# programmer.net
KiCad netlist of a schematic drawn in EAGLE
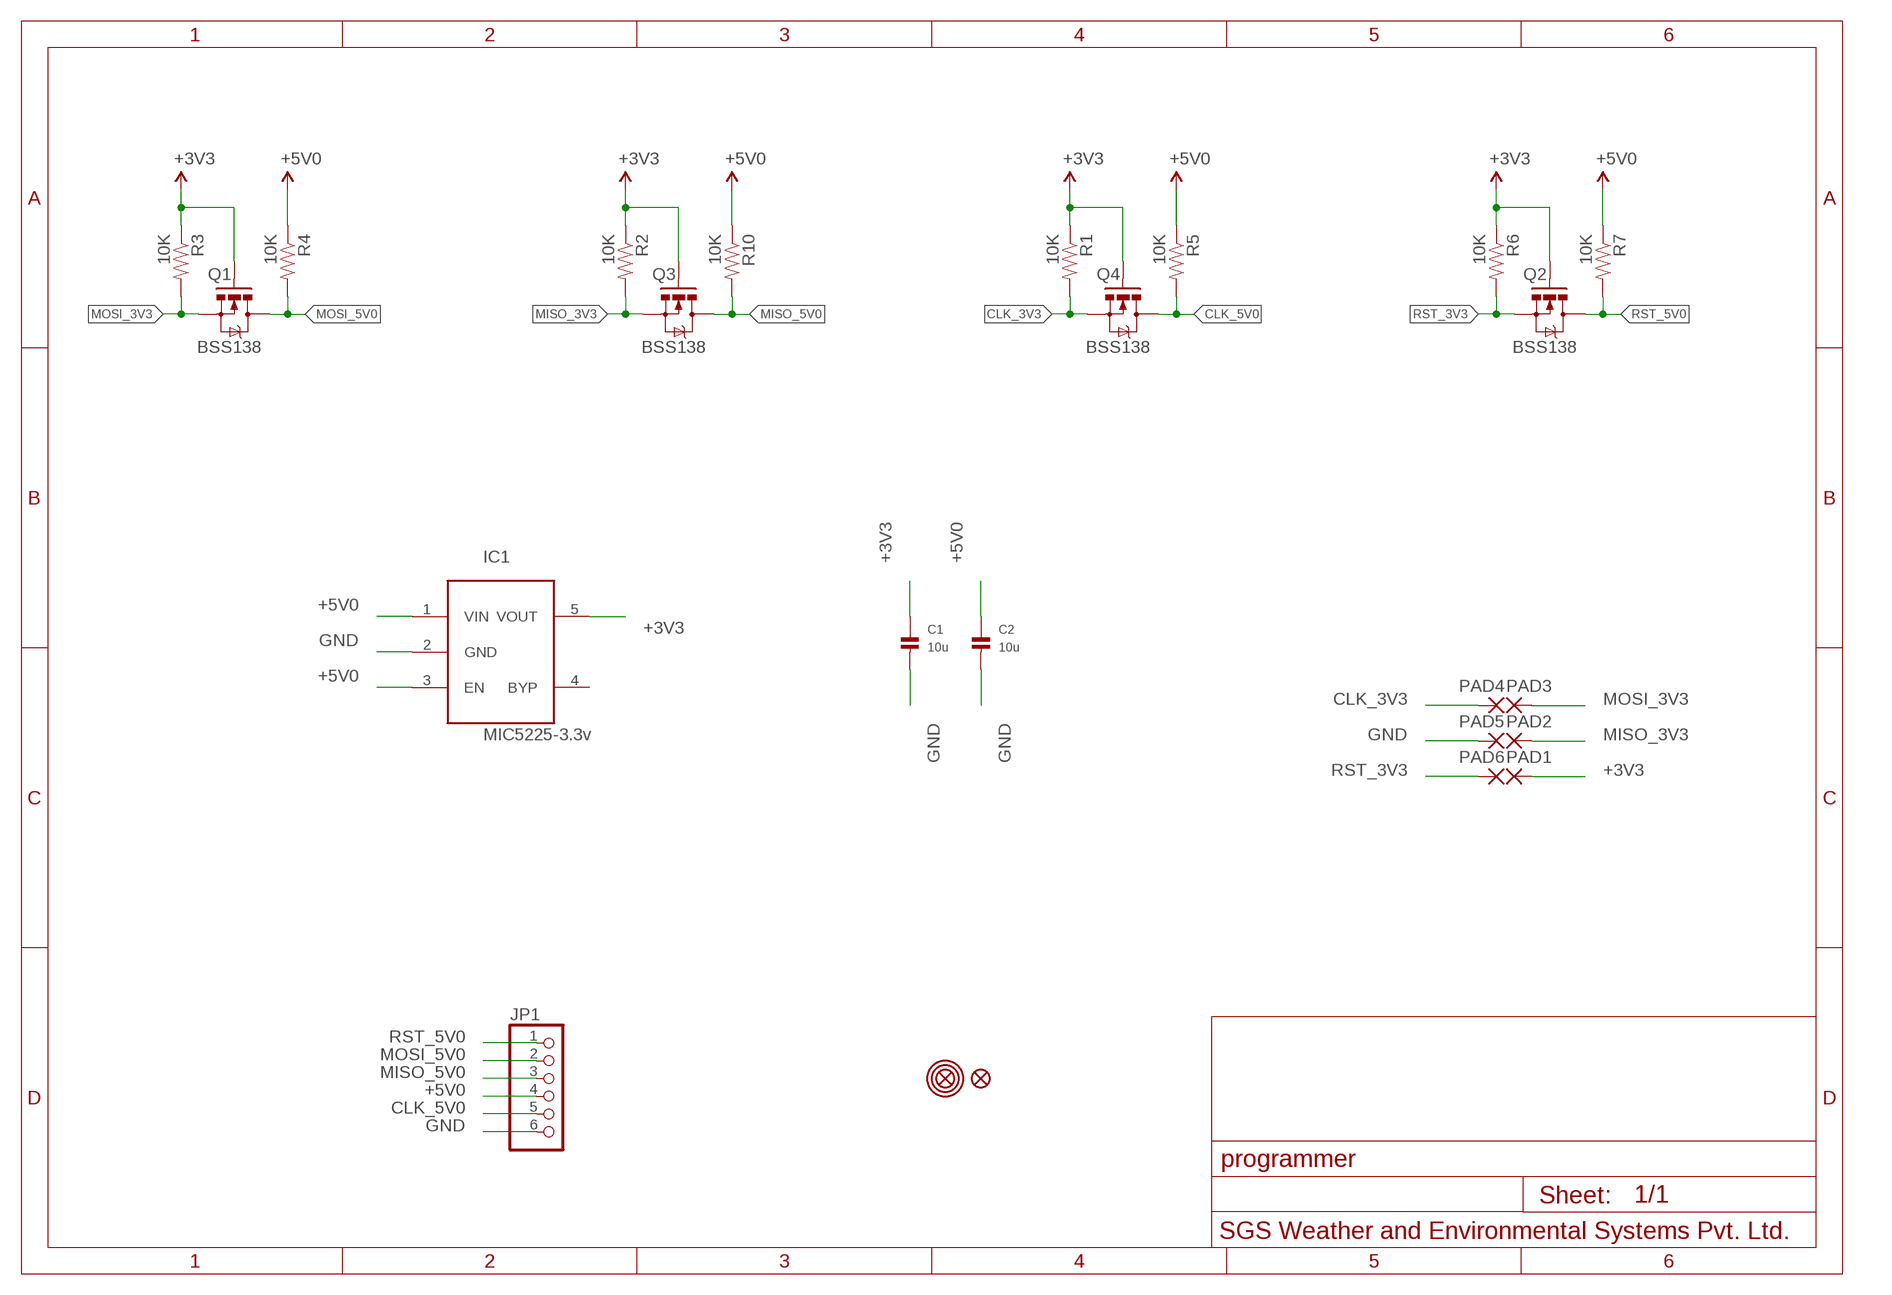
[diagram p0: schematic, sheet 1]

(export (version "E")
  (design (tool "Eeschema 10.0.6"))
  (components
    (comp (ref "C1")
      (value "10u")
      (footprint "eagle-import:0603")
      (libsource (lib "eagle-import") (part "CAP_CERAMIC0603"))
    )
    (comp (ref "C2")
      (value "10u")
      (footprint "eagle-import:0603")
      (libsource (lib "eagle-import") (part "CAP_CERAMIC0603"))
    )
    (comp (ref "FID1")
      (value "FIDUCIAL1X2.5")
      (footprint "eagle-import:FIDUCIAL-1X2.5")
      (libsource (lib "eagle-import") (part "FIDUCIAL1X2.5"))
    )
    (comp (ref "FID2")
      (value "FIDUCIAL1X2.5")
      (footprint "eagle-import:FIDUCIAL-1X2.5")
      (libsource (lib "eagle-import") (part "FIDUCIAL1X2.5"))
    )
    (comp (ref "IC1")
      (value "MIC5225-3.3v")
      (footprint "eagle-import:SOT23-5L")
      (libsource (lib "eagle-import") (part "LP298XS"))
    )
    (comp (ref "JP1")
      (value "HEADER-1X6ROUND")
      (footprint "eagle-import:1X06_ROUND")
      (libsource (lib "eagle-import") (part "HEADER-1X6ROUND"))
    )
    (comp (ref "PAD1")
      (value "WIREPADSMD1,27-254")
      (footprint "eagle-import:SMD1,27-2,54")
      (libsource (lib "eagle-import") (part "WIREPADSMD1,27-254"))
    )
    (comp (ref "PAD2")
      (value "WIREPADSMD1,27-254")
      (footprint "eagle-import:SMD1,27-2,54")
      (libsource (lib "eagle-import") (part "WIREPADSMD1,27-254"))
    )
    (comp (ref "PAD3")
      (value "WIREPADSMD1,27-254")
      (footprint "eagle-import:SMD1,27-2,54")
      (libsource (lib "eagle-import") (part "WIREPADSMD1,27-254"))
    )
    (comp (ref "PAD4")
      (value "WIREPADSMD1,27-254")
      (footprint "eagle-import:SMD1,27-2,54")
      (libsource (lib "eagle-import") (part "WIREPADSMD1,27-254"))
    )
    (comp (ref "PAD5")
      (value "WIREPADSMD1,27-254")
      (footprint "eagle-import:SMD1,27-2,54")
      (libsource (lib "eagle-import") (part "WIREPADSMD1,27-254"))
    )
    (comp (ref "PAD6")
      (value "WIREPADSMD1,27-254")
      (footprint "eagle-import:SMD1,27-2,54")
      (libsource (lib "eagle-import") (part "WIREPADSMD1,27-254"))
    )
    (comp (ref "Q1")
      (value "BSS138")
      (footprint "eagle-import:SOT23-3")
      (libsource (lib "eagle-import") (part "MOSFET-NCHANNELSMD"))
    )
    (comp (ref "Q2")
      (value "BSS138")
      (footprint "eagle-import:SOT23-3")
      (libsource (lib "eagle-import") (part "MOSFET-NCHANNELSMD"))
    )
    (comp (ref "Q3")
      (value "BSS138")
      (footprint "eagle-import:SOT23-3")
      (libsource (lib "eagle-import") (part "MOSFET-NCHANNELSMD"))
    )
    (comp (ref "Q4")
      (value "BSS138")
      (footprint "eagle-import:SOT23-3")
      (libsource (lib "eagle-import") (part "MOSFET-NCHANNELSMD"))
    )
    (comp (ref "R1")
      (value "10K")
      (footprint "eagle-import:0603-RES")
      (libsource (lib "eagle-import") (part "RESISTOR0603-RES"))
    )
    (comp (ref "R2")
      (value "10K")
      (footprint "eagle-import:0603-RES")
      (libsource (lib "eagle-import") (part "RESISTOR0603-RES"))
    )
    (comp (ref "R3")
      (value "10K")
      (footprint "eagle-import:0603-RES")
      (libsource (lib "eagle-import") (part "RESISTOR0603-RES"))
    )
    (comp (ref "R4")
      (value "10K")
      (footprint "eagle-import:0603-RES")
      (libsource (lib "eagle-import") (part "RESISTOR0603-RES"))
    )
    (comp (ref "R5")
      (value "10K")
      (footprint "eagle-import:0603-RES")
      (libsource (lib "eagle-import") (part "RESISTOR0603-RES"))
    )
    (comp (ref "R6")
      (value "10K")
      (footprint "eagle-import:0603-RES")
      (libsource (lib "eagle-import") (part "RESISTOR0603-RES"))
    )
    (comp (ref "R7")
      (value "10K")
      (footprint "eagle-import:0603-RES")
      (libsource (lib "eagle-import") (part "RESISTOR0603-RES"))
    )
    (comp (ref "R10")
      (value "10K")
      (footprint "eagle-import:0603-RES")
      (libsource (lib "eagle-import") (part "RESISTOR0603-RES"))
    )
    (comp (ref "U$1")
      (value "MOUNTINGHOLE2.5")
      (footprint "eagle-import:MOUNTINGHOLE_2.5_PLATED")
      (libsource (lib "eagle-import") (part "MOUNTINGHOLE2.5"))
    )
  )
  (nets
    (net (code "1") (name "+3V3") (class "Default")
      (node (ref "C1") (pin "1") (pinfunction "P$1_1") (pintype "passive"))
      (node (ref "IC1") (pin "5") (pinfunction "VOUT_5") (pintype "bidirectional"))
      (node (ref "PAD1") (pin "1") (pinfunction "P_1") (pintype "passive"))
      (node (ref "Q1") (pin "1") (pinfunction "G_1") (pintype "passive"))
      (node (ref "Q2") (pin "1") (pinfunction "G_1") (pintype "passive"))
      (node (ref "Q3") (pin "1") (pinfunction "G_1") (pintype "passive"))
      (node (ref "Q4") (pin "1") (pinfunction "G_1") (pintype "passive"))
      (node (ref "R1") (pin "1") (pinfunction "1_1") (pintype "passive"))
      (node (ref "R2") (pin "1") (pinfunction "1_1") (pintype "passive"))
      (node (ref "R3") (pin "1") (pinfunction "1_1") (pintype "passive"))
      (node (ref "R6") (pin "1") (pinfunction "1_1") (pintype "passive"))
    )
    (net (code "2") (name "+5V0") (class "Default")
      (node (ref "C2") (pin "1") (pinfunction "P$1_1") (pintype "passive"))
      (node (ref "IC1") (pin "1") (pinfunction "VIN_1") (pintype "bidirectional"))
      (node (ref "IC1") (pin "3") (pinfunction "EN_3") (pintype "bidirectional"))
      (node (ref "JP1") (pin "4") (pinfunction "4_4") (pintype "passive"))
      (node (ref "R10") (pin "1") (pinfunction "1_1") (pintype "passive"))
      (node (ref "R4") (pin "1") (pinfunction "1_1") (pintype "passive"))
      (node (ref "R5") (pin "1") (pinfunction "1_1") (pintype "passive"))
      (node (ref "R7") (pin "1") (pinfunction "1_1") (pintype "passive"))
    )
    (net (code "3") (name "/GND") (class "Default")
      (node (ref "C1") (pin "2") (pinfunction "P$2_2") (pintype "passive"))
      (node (ref "C2") (pin "2") (pinfunction "P$2_2") (pintype "passive"))
      (node (ref "IC1") (pin "2") (pinfunction "GND_2") (pintype "bidirectional"))
      (node (ref "JP1") (pin "6") (pinfunction "6_6") (pintype "passive"))
      (node (ref "PAD5") (pin "1") (pinfunction "P_1") (pintype "passive"))
    )
    (net (code "4") (name "CLK_3V3") (class "Default")
      (node (ref "PAD4") (pin "1") (pinfunction "P_1") (pintype "passive"))
      (node (ref "Q4") (pin "2") (pinfunction "S_2") (pintype "passive"))
      (node (ref "R1") (pin "2") (pinfunction "2_2") (pintype "passive"))
    )
    (net (code "5") (name "CLK_5V0") (class "Default")
      (node (ref "JP1") (pin "5") (pinfunction "5_5") (pintype "passive"))
      (node (ref "Q4") (pin "3") (pinfunction "D_3") (pintype "passive"))
      (node (ref "R5") (pin "2") (pinfunction "2_2") (pintype "passive"))
    )
    (net (code "6") (name "MISO_3V3") (class "Default")
      (node (ref "PAD2") (pin "1") (pinfunction "P_1") (pintype "passive"))
      (node (ref "Q3") (pin "2") (pinfunction "S_2") (pintype "passive"))
      (node (ref "R2") (pin "2") (pinfunction "2_2") (pintype "passive"))
    )
    (net (code "7") (name "MISO_5V0") (class "Default")
      (node (ref "JP1") (pin "3") (pinfunction "3_3") (pintype "passive"))
      (node (ref "Q3") (pin "3") (pinfunction "D_3") (pintype "passive"))
      (node (ref "R10") (pin "2") (pinfunction "2_2") (pintype "passive"))
    )
    (net (code "8") (name "MOSI_3V3") (class "Default")
      (node (ref "PAD3") (pin "1") (pinfunction "P_1") (pintype "passive"))
      (node (ref "Q1") (pin "2") (pinfunction "S_2") (pintype "passive"))
      (node (ref "R3") (pin "2") (pinfunction "2_2") (pintype "passive"))
    )
    (net (code "9") (name "MOSI_5V0") (class "Default")
      (node (ref "JP1") (pin "2") (pinfunction "2_2") (pintype "passive"))
      (node (ref "Q1") (pin "3") (pinfunction "D_3") (pintype "passive"))
      (node (ref "R4") (pin "2") (pinfunction "2_2") (pintype "passive"))
    )
    (net (code "10") (name "RST_3V3") (class "Default")
      (node (ref "PAD6") (pin "1") (pinfunction "P_1") (pintype "passive"))
      (node (ref "Q2") (pin "2") (pinfunction "S_2") (pintype "passive"))
      (node (ref "R6") (pin "2") (pinfunction "2_2") (pintype "passive"))
    )
    (net (code "11") (name "RST_5V0") (class "Default")
      (node (ref "JP1") (pin "1") (pinfunction "1_1") (pintype "passive"))
      (node (ref "Q2") (pin "3") (pinfunction "D_3") (pintype "passive"))
      (node (ref "R7") (pin "2") (pinfunction "2_2") (pintype "passive"))
    )
    (net (code "12") (name "unconnected-(IC1-BYP-Pad4)") (class "Default")
      (node (ref "IC1") (pin "4") (pinfunction "BYP_4") (pintype "bidirectional"))
    )
  )
)
